# ADS-B_LNA_Bias-T.net
KiCad netlist of a schematic drawn in EAGLE
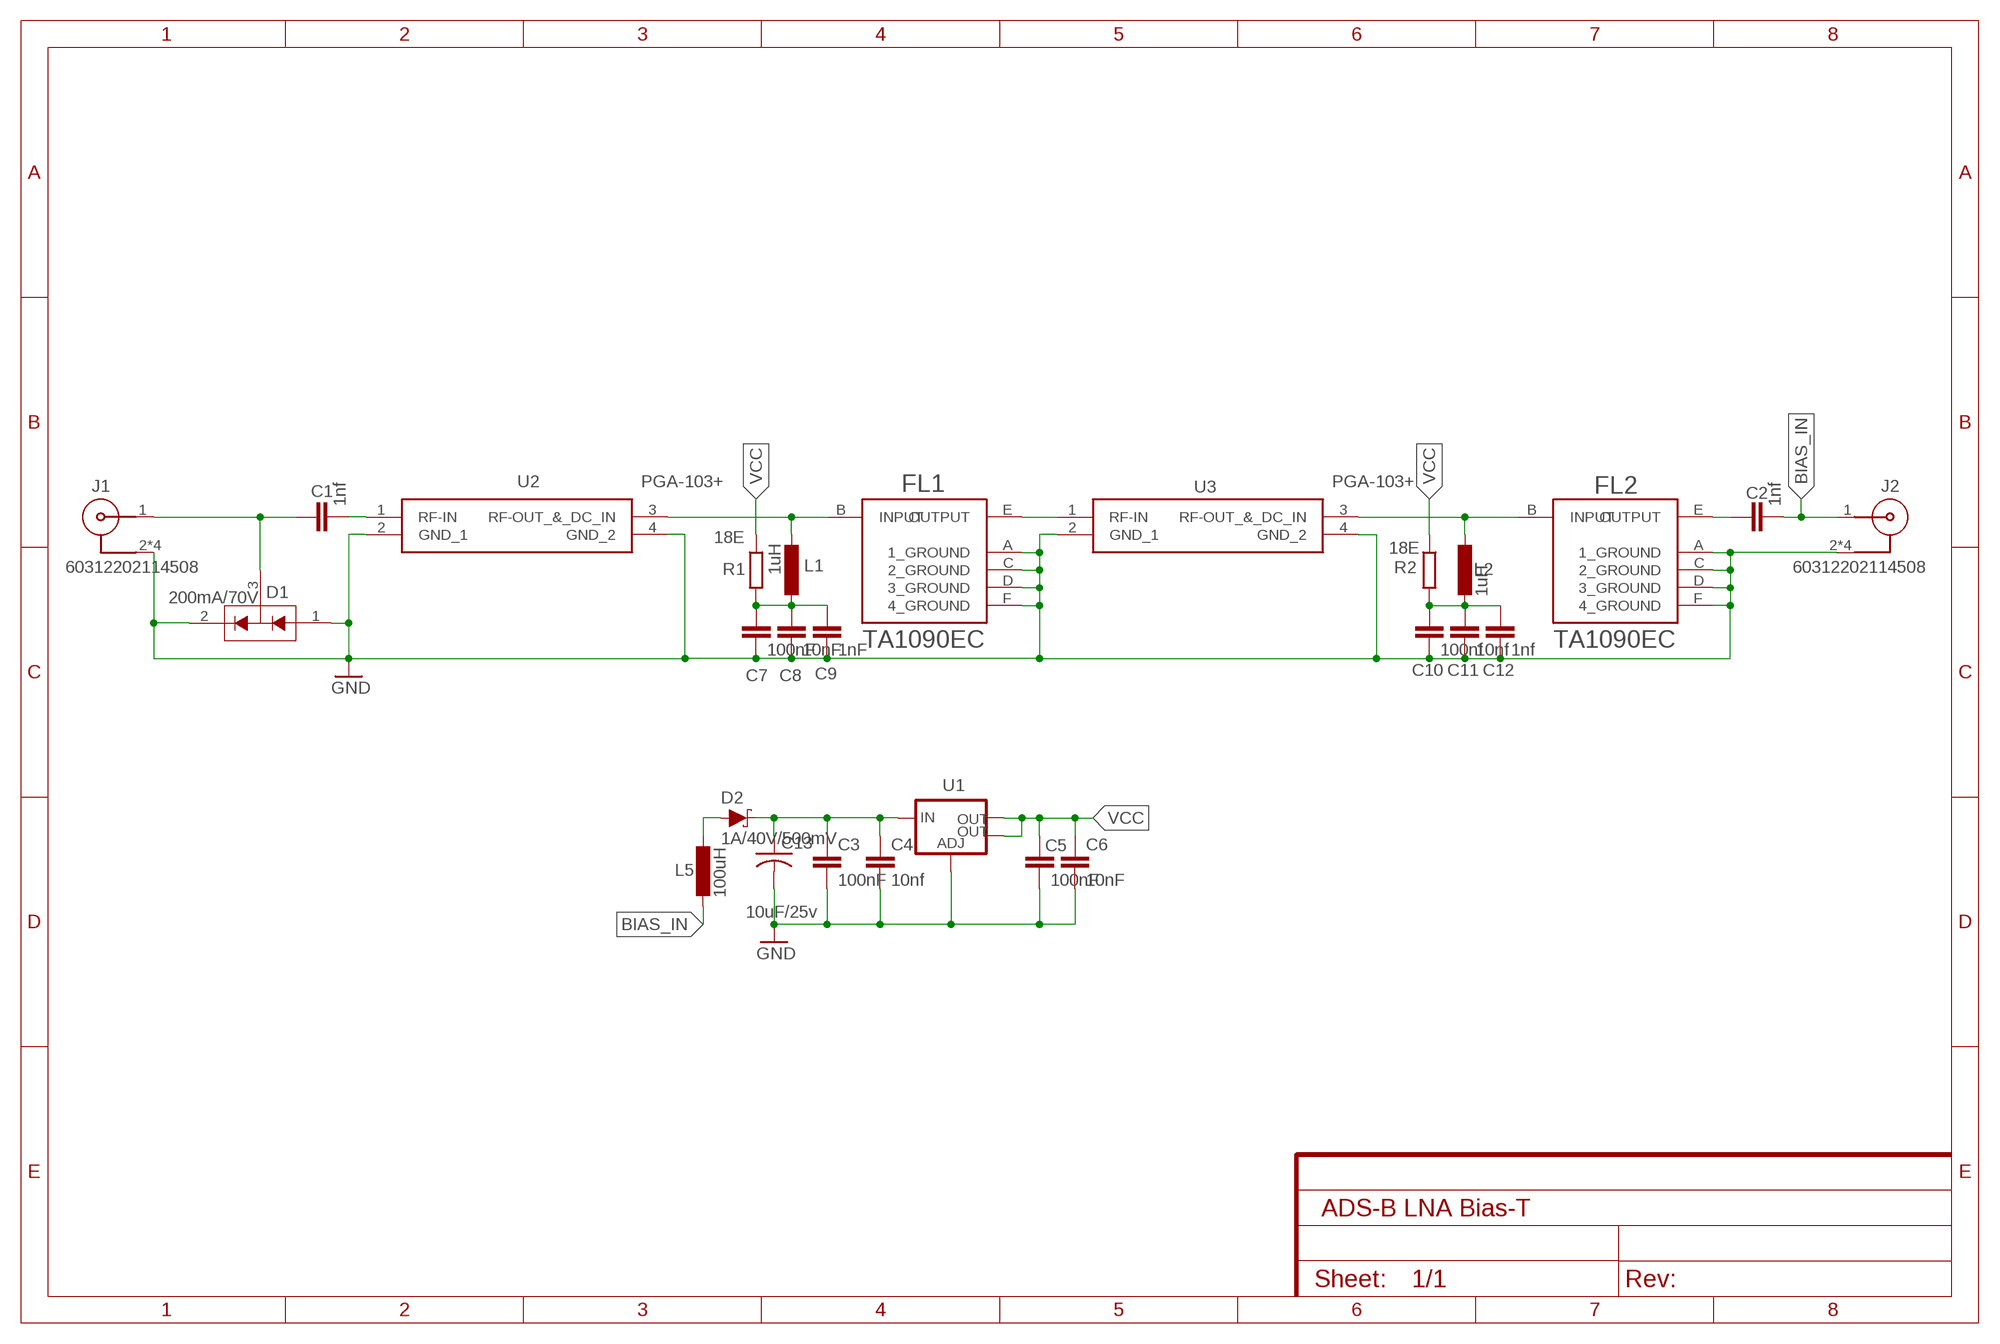
[diagram p0: schematic, sheet 1]

(export (version "E")
  (design (tool "Eeschema 10.0.6"))
  (components
    (comp (ref "C1")
      (value "1nf")
      (footprint "eagle-import:C0603K")
      (libsource (lib "eagle-import") (part "C-EUC0603K"))
    )
    (comp (ref "C2")
      (value "1nf")
      (footprint "eagle-import:C0603K")
      (libsource (lib "eagle-import") (part "C-EUC0603K"))
    )
    (comp (ref "C3")
      (value "100nF")
      (footprint "eagle-import:C0603K")
      (libsource (lib "eagle-import") (part "C-EUC0603K"))
    )
    (comp (ref "C4")
      (value "10nf")
      (footprint "eagle-import:C0603K")
      (libsource (lib "eagle-import") (part "C-EUC0603K"))
    )
    (comp (ref "C5")
      (value "100nF")
      (footprint "eagle-import:C0603K")
      (libsource (lib "eagle-import") (part "C-EUC0603K"))
    )
    (comp (ref "C6")
      (value "10nF")
      (footprint "eagle-import:C0603K")
      (libsource (lib "eagle-import") (part "C-EUC0603K"))
    )
    (comp (ref "C7")
      (value "100nF")
      (footprint "eagle-import:C0603K")
      (libsource (lib "eagle-import") (part "C-EUC0603K"))
    )
    (comp (ref "C8")
      (value "10nF")
      (footprint "eagle-import:C0603K")
      (libsource (lib "eagle-import") (part "C-EUC0603K"))
    )
    (comp (ref "C9")
      (value "1nF")
      (footprint "eagle-import:C0603K")
      (libsource (lib "eagle-import") (part "C-EUC0603K"))
    )
    (comp (ref "C10")
      (value "100nf")
      (footprint "eagle-import:C0603K")
      (libsource (lib "eagle-import") (part "C-EUC0603K"))
    )
    (comp (ref "C11")
      (value "10nf")
      (footprint "eagle-import:C0603K")
      (libsource (lib "eagle-import") (part "C-EUC0603K"))
    )
    (comp (ref "C12")
      (value "1nf")
      (footprint "eagle-import:C0603K")
      (libsource (lib "eagle-import") (part "C-EUC0603K"))
    )
    (comp (ref "C13")
      (value "10uF/25v")
      (footprint "eagle-import:C3216")
      (libsource (lib "eagle-import") (part "C-USC3216"))
    )
    (comp (ref "D1")
      (value "200mA/70V")
      (footprint "eagle-import:SOT23-3")
      (libsource (lib "eagle-import") (part "BAV99"))
    )
    (comp (ref "D2")
      (value "1A/40V/500mV")
      (footprint "eagle-import:SMA-DIODE")
      (libsource (lib "eagle-import") (part "DIODE-SCHOTTKY-SS14"))
    )
    (comp (ref "FL1")
      (value "TAI-SAW_TECHNOLOGY_TA1090ECTAI-SAW_TECHNOLOGY_TA1090EC_0_0")
      (footprint "eagle-import:TAI-SAW_TECHNOLOGY_TA1090EC_0")
      (fields
        (field (name "MF") "Tai-Saw Technology")
        (field (name "MPN") "TA1090EC")
        (field (name "OCTOPART_PART_NUMBER") "42898a0e4c549d4e")
      )
      (libsource (lib "eagle-import") (part "TAI-SAW_TECHNOLOGY_TA1090ECTAI-SAW_TECHNOLOGY_TA1090EC_0_0"))
    )
    (comp (ref "FL2")
      (value "TAI-SAW_TECHNOLOGY_TA1090ECTAI-SAW_TECHNOLOGY_TA1090EC_0_0")
      (footprint "eagle-import:TAI-SAW_TECHNOLOGY_TA1090EC_0")
      (fields
        (field (name "MF") "Tai-Saw Technology")
        (field (name "MPN") "TA1090EC")
        (field (name "OCTOPART_PART_NUMBER") "42898a0e4c549d4e")
      )
      (libsource (lib "eagle-import") (part "TAI-SAW_TECHNOLOGY_TA1090ECTAI-SAW_TECHNOLOGY_TA1090EC_0_0"))
    )
    (comp (ref "J1")
      (value "60312202114508")
      (footprint "eagle-import:60312202114508")
      (fields (field (name "MF") "Würth Elektronik"))
      (libsource (lib "eagle-import") (part "60312202114508"))
    )
    (comp (ref "J2")
      (value "60312202114508")
      (footprint "eagle-import:60312202114508")
      (fields (field (name "MF") "Würth Elektronik"))
      (libsource (lib "eagle-import") (part "60312202114508"))
    )
    (comp (ref "L1")
      (value "1uH")
      (footprint "eagle-import:L3230M")
      (libsource (lib "eagle-import") (part "resistor_348_L-EUL3230M"))
    )
    (comp (ref "L2")
      (value "1uH")
      (footprint "eagle-import:L3225M")
      (libsource (lib "eagle-import") (part "L-EUL3225M"))
    )
    (comp (ref "L5")
      (value "100uH")
      (footprint "eagle-import:L4532M")
      (libsource (lib "eagle-import") (part "L-EUL4532C"))
    )
    (comp (ref "R1")
      (value "18E")
      (footprint "eagle-import:R1206")
      (libsource (lib "eagle-import") (part "R-EU_R1206"))
    )
    (comp (ref "R2")
      (value "18E")
      (footprint "eagle-import:R1206")
      (libsource (lib "eagle-import") (part "R-EU_R1206"))
    )
    (comp (ref "U1")
      (value "V_REG_LM1117SOT223")
      (footprint "eagle-import:SOT223")
      (libsource (lib "eagle-import") (part "V_REG_LM1117SOT223"))
    )
    (comp (ref "U2")
      (value "PGA-103+")
      (footprint "eagle-import:GVA63")
      (fields (field (name "MOUSER_PART_NUMBER") "139-PGA-103"))
      (libsource (lib "eagle-import") (part "PGA-103+"))
    )
    (comp (ref "U3")
      (value "PGA-103+")
      (footprint "eagle-import:GVA63")
      (fields (field (name "MOUSER_PART_NUMBER") "139-PGA-103"))
      (libsource (lib "eagle-import") (part "PGA-103+"))
    )
  )
  (nets
    (net (code "1") (name "BIAS_IN") (class "Default")
      (node (ref "C2") (pin "2") (pinfunction "2_2") (pintype "passive"))
      (node (ref "J2") (pin "1") (pinfunction "1_1") (pintype "passive"))
      (node (ref "L5") (pin "2") (pinfunction "2_2") (pintype "passive"))
    )
    (net (code "2") (name "GND") (class "Default")
      (node (ref "C10") (pin "2") (pinfunction "2_2") (pintype "passive"))
      (node (ref "C11") (pin "2") (pinfunction "2_2") (pintype "passive"))
      (node (ref "C12") (pin "2") (pinfunction "2_2") (pintype "passive"))
      (node (ref "C13") (pin "2") (pinfunction "2_2") (pintype "passive"))
      (node (ref "C3") (pin "2") (pinfunction "2_2") (pintype "passive"))
      (node (ref "C4") (pin "2") (pinfunction "2_2") (pintype "passive"))
      (node (ref "C5") (pin "2") (pinfunction "2_2") (pintype "passive"))
      (node (ref "C6") (pin "2") (pinfunction "2_2") (pintype "passive"))
      (node (ref "C7") (pin "2") (pinfunction "2_2") (pintype "passive"))
      (node (ref "C8") (pin "2") (pinfunction "2_2") (pintype "passive"))
      (node (ref "C9") (pin "2") (pinfunction "2_2") (pintype "passive"))
      (node (ref "D1") (pin "1") (pinfunction "A1_1") (pintype "bidirectional"))
      (node (ref "D1") (pin "2") (pinfunction "C2_2") (pintype "bidirectional"))
      (node (ref "FL1") (pin "A") (pinfunction "1_GROUND_A") (pintype "bidirectional"))
      (node (ref "FL1") (pin "C") (pinfunction "2_GROUND_C") (pintype "bidirectional"))
      (node (ref "FL1") (pin "D") (pinfunction "3_GROUND_D") (pintype "bidirectional"))
      (node (ref "FL1") (pin "F") (pinfunction "4_GROUND_F") (pintype "bidirectional"))
      (node (ref "FL2") (pin "A") (pinfunction "1_GROUND_A") (pintype "bidirectional"))
      (node (ref "FL2") (pin "C") (pinfunction "2_GROUND_C") (pintype "bidirectional"))
      (node (ref "FL2") (pin "D") (pinfunction "3_GROUND_D") (pintype "bidirectional"))
      (node (ref "FL2") (pin "F") (pinfunction "4_GROUND_F") (pintype "bidirectional"))
      (node (ref "J1") (pin "2") (pinfunction "2_2") (pintype "passive"))
      (node (ref "J1") (pin "3") (pinfunction "2_3") (pintype "passive"))
      (node (ref "J1") (pin "4") (pinfunction "2_4") (pintype "passive"))
      (node (ref "J1") (pin "5") (pinfunction "2_5") (pintype "passive"))
      (node (ref "J2") (pin "2") (pinfunction "2_2") (pintype "passive"))
      (node (ref "J2") (pin "3") (pinfunction "2_3") (pintype "passive"))
      (node (ref "J2") (pin "4") (pinfunction "2_4") (pintype "passive"))
      (node (ref "J2") (pin "5") (pinfunction "2_5") (pintype "passive"))
      (node (ref "U1") (pin "1") (pinfunction "ADJ_1") (pintype "input"))
      (node (ref "U2") (pin "2") (pinfunction "GND_1_2") (pintype "bidirectional"))
      (node (ref "U2") (pin "4") (pinfunction "GND_2_4") (pintype "bidirectional"))
      (node (ref "U3") (pin "2") (pinfunction "GND_1_2") (pintype "bidirectional"))
      (node (ref "U3") (pin "4") (pinfunction "GND_2_4") (pintype "bidirectional"))
    )
    (net (code "3") (name "Net-(C7-Pad1)") (class "Default")
      (node (ref "C7") (pin "1") (pinfunction "1_1") (pintype "passive"))
      (node (ref "C8") (pin "1") (pinfunction "1_1") (pintype "passive"))
      (node (ref "C9") (pin "1") (pinfunction "1_1") (pintype "passive"))
      (node (ref "L1") (pin "1") (pinfunction "1_1") (pintype "passive"))
      (node (ref "R1") (pin "2") (pinfunction "2_2") (pintype "passive"))
    )
    (net (code "4") (name "Net-(C10-Pad1)") (class "Default")
      (node (ref "C10") (pin "1") (pinfunction "1_1") (pintype "passive"))
      (node (ref "C11") (pin "1") (pinfunction "1_1") (pintype "passive"))
      (node (ref "C12") (pin "1") (pinfunction "1_1") (pintype "passive"))
      (node (ref "L2") (pin "2") (pinfunction "2_2") (pintype "passive"))
      (node (ref "R2") (pin "2") (pinfunction "2_2") (pintype "passive"))
    )
    (net (code "5") (name "Net-(D1-COM)") (class "Default")
      (node (ref "C1") (pin "1") (pinfunction "1_1") (pintype "passive"))
      (node (ref "D1") (pin "3") (pinfunction "COM_3") (pintype "bidirectional"))
      (node (ref "J1") (pin "1") (pinfunction "1_1") (pintype "passive"))
    )
    (net (code "6") (name "Net-(D2-PadA)") (class "Default")
      (node (ref "D2") (pin "A") (pinfunction "A_A") (pintype "passive"))
      (node (ref "L5") (pin "1") (pinfunction "1_1") (pintype "passive"))
    )
    (net (code "7") (name "Net-(FL1-INPUT)") (class "Default")
      (node (ref "FL1") (pin "B") (pinfunction "INPUT_B") (pintype "bidirectional"))
      (node (ref "L1") (pin "2") (pinfunction "2_2") (pintype "passive"))
      (node (ref "U2") (pin "3") (pinfunction "RF-OUT_&_DC_IN_3") (pintype "bidirectional"))
    )
    (net (code "8") (name "Net-(FL1-OUTPUT)") (class "Default")
      (node (ref "FL1") (pin "E") (pinfunction "OUTPUT_E") (pintype "bidirectional"))
      (node (ref "U3") (pin "1") (pinfunction "RF-IN_1") (pintype "bidirectional"))
    )
    (net (code "9") (name "Net-(FL2-INPUT)") (class "Default")
      (node (ref "FL2") (pin "B") (pinfunction "INPUT_B") (pintype "bidirectional"))
      (node (ref "L2") (pin "1") (pinfunction "1_1") (pintype "passive"))
      (node (ref "U3") (pin "3") (pinfunction "RF-OUT_&_DC_IN_3") (pintype "bidirectional"))
    )
    (net (code "10") (name "Net-(FL2-OUTPUT)") (class "Default")
      (node (ref "C2") (pin "1") (pinfunction "1_1") (pintype "passive"))
      (node (ref "FL2") (pin "E") (pinfunction "OUTPUT_E") (pintype "bidirectional"))
    )
    (net (code "11") (name "Net-(U1-IN)") (class "Default")
      (node (ref "C13") (pin "1") (pinfunction "1_1") (pintype "passive"))
      (node (ref "C3") (pin "1") (pinfunction "1_1") (pintype "passive"))
      (node (ref "C4") (pin "1") (pinfunction "1_1") (pintype "passive"))
      (node (ref "D2") (pin "C") (pinfunction "C_C") (pintype "passive"))
      (node (ref "U1") (pin "3") (pinfunction "IN_3") (pintype "input"))
    )
    (net (code "12") (name "Net-(U2-RF-IN)") (class "Default")
      (node (ref "C1") (pin "2") (pinfunction "2_2") (pintype "passive"))
      (node (ref "U2") (pin "1") (pinfunction "RF-IN_1") (pintype "bidirectional"))
    )
    (net (code "13") (name "VCC") (class "Default")
      (node (ref "C5") (pin "1") (pinfunction "1_1") (pintype "passive"))
      (node (ref "C6") (pin "1") (pinfunction "1_1") (pintype "passive"))
      (node (ref "R1") (pin "1") (pinfunction "1_1") (pintype "passive"))
      (node (ref "R2") (pin "1") (pinfunction "1_1") (pintype "passive"))
      (node (ref "U1") (pin "2") (pinfunction "OUT_2") (pintype "output"))
      (node (ref "U1") (pin "4") (pinfunction "OUT_4") (pintype "output"))
    )
  )
)
